# STEP-UP.net
KiCad netlist of a schematic drawn in Altium Designer
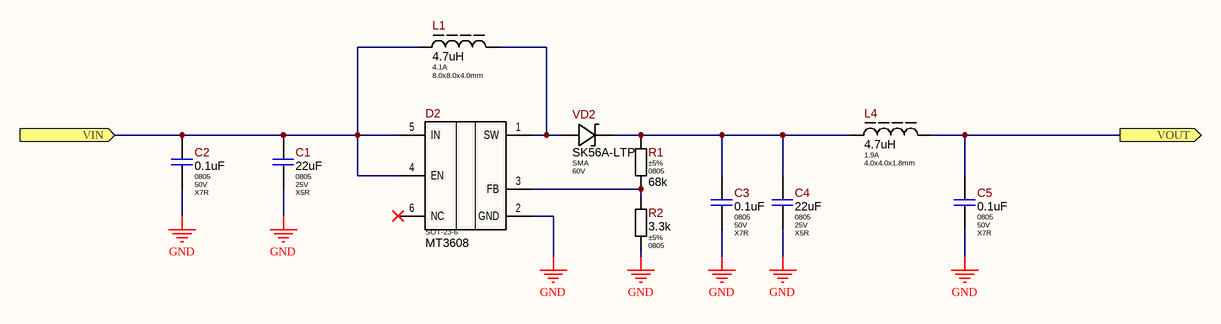
[diagram p0: STEP-UP.SchDoc]

(export (version "E")
  (design (tool "Eeschema 10.0.6"))
  (components
    (comp (ref "C1")
      (value "22uF")
      (footprint "CAP-0805(2012)X125T20")
      (description "22uF 25V X5R ±20% 0805 Ceramic Capacitor RoHS")
      (fields
        (field (name "PACKAGE") "0805")
        (field (name "VOLTAGE") "25V")
        (field (name "DIELECTRIC TYPE") "X5R")
        (field (name "PART NUMBER") "CL21A226MAYNNNE")
        (field (name "MANUFACTURER") "Samsung Electro-Mechanics")
      )
      (libsource (lib "capacitors") (part "CL21A226MAYNNNE"))
    )
    (comp (ref "C2")
      (value "0.1uF")
      (footprint "CAP-0805(2012)X85T10")
      (description "100nF 50V X7R ±10% 0805 Ceramic Capacitor RoHS")
      (fields
        (field (name "PACKAGE") "0805")
        (field (name "VOLTAGE") "50V")
        (field (name "DIELECTRIC TYPE") "X7R")
        (field (name "PART NUMBER") "CL21B104KBCNNNC")
        (field (name "MANUFACTURER") "Samsung Electro-Mechanics")
      )
      (libsource (lib "capacitors") (part "CL21B104KBCNNNC"))
    )
    (comp (ref "C3")
      (value "0.1uF")
      (footprint "CAP-0805(2012)X85T10")
      (description "100nF 50V X7R ±10% 0805 Ceramic Capacitor RoHS")
      (fields
        (field (name "PACKAGE") "0805")
        (field (name "VOLTAGE") "50V")
        (field (name "DIELECTRIC TYPE") "X7R")
        (field (name "PART NUMBER") "CL21B104KBCNNNC")
        (field (name "MANUFACTURER") "Samsung Electro-Mechanics")
      )
      (libsource (lib "capacitors") (part "CL21B104KBCNNNC"))
    )
    (comp (ref "C4")
      (value "22uF")
      (footprint "CAP-0805(2012)X125T20")
      (description "22uF 25V X5R ±20% 0805 Ceramic Capacitor RoHS")
      (fields
        (field (name "PACKAGE") "0805")
        (field (name "VOLTAGE") "25V")
        (field (name "DIELECTRIC TYPE") "X5R")
        (field (name "PART NUMBER") "CL21A226MAYNNNE")
        (field (name "MANUFACTURER") "Samsung Electro-Mechanics")
      )
      (libsource (lib "capacitors") (part "CL21A226MAYNNNE"))
    )
    (comp (ref "C5")
      (value "0.1uF")
      (footprint "CAP-0805(2012)X85T10")
      (description "100nF 50V X7R ±10% 0805 Ceramic Capacitor RoHS")
      (fields
        (field (name "PACKAGE") "0805")
        (field (name "VOLTAGE") "50V")
        (field (name "DIELECTRIC TYPE") "X7R")
        (field (name "PART NUMBER") "CL21B104KBCNNNC")
        (field (name "MANUFACTURER") "Samsung Electro-Mechanics")
      )
      (libsource (lib "capacitors") (part "CL21B104KBCNNNC"))
    )
    (comp (ref "D2")
      (value "MT3608")
      (footprint "MT3608_MED")
      (description "2V-24V Input High Efficiency 1.2MHz 2A Step Up Converter")
      (fields
        (field (name "PACKAGE") "SOT-23-6")
        (field (name "PART NUMBER") "MT3608")
        (field (name "MANUFACTURER") "Aerosemi")
      )
      (libsource (lib "ic") (part "MT3608"))
    )
    (comp (ref "L1")
      (value "4.7uH")
      (footprint "SWPA8040S-Series")
      (description "4.7uH Magnetic-Resin Shielded Wirewound Inductor 4.1 A 25mOhm Max")
      (fields
        (field (name "CURRENT") "4.1A")
        (field (name "PACKAGE") "8.0x8.0x4.0mm")
        (field (name "PART NUMBER") "SWPA8040S4R7NT")
        (field (name "TOLERANCE") "±30%")
      )
      (libsource (lib "inductors") (part "SWPA8040S4R7NT"))
    )
    (comp (ref "L4")
      (value "4.7uH")
      (footprint "SRN4018-Series_1.8mm")
      (description "4.7uH Semi-Shielded Wirewound Inductor 1.9A 84mOhm Max")
      (fields
        (field (name "CURRENT") "1.9A")
        (field (name "PACKAGE") "4.0x4.0x1.8mm")
        (field (name "PART NUMBER") "SRN4018-4R7M")
        (field (name "TOLERANCE") "±20%")
      )
      (libsource (lib "inductors") (part "SRN4018-4R7M"))
    )
    (comp (ref "R1")
      (value "68k")
      (footprint "R_ANY_CHIP_0805_MED")
      (description "2.2 kOhms ±5% 1/8W 0805 Thick Film Resistor")
      (fields
        (field (name "TOLERANCE") "±5%")
        (field (name "PACKAGE") "0805")
        (field (name "PART NUMBER") "RC0805JR-072K2L")
        (field (name "MANUFACTURER") "Yageo")
      )
      (libsource (lib "resistors") (part "RC0805JR-072K2L"))
    )
    (comp (ref "R2")
      (value "3.3k")
      (footprint "R_ANY_CHIP_0805_MED")
      (description "3.3 kOhms ±5%, 1/8W 0805 Thick Film Resistor")
      (fields
        (field (name "TOLERANCE") "±5%")
        (field (name "PACKAGE") "0805")
        (field (name "PART NUMBER") "RC0805JR-073K3L")
        (field (name "MANUFACTURER") "Yageo")
      )
      (libsource (lib "resistors") (part "RC0805JR-073K3L"))
    )
    (comp (ref "VD2")
      (value "SK56A-LTP")
      (footprint "SMA_MED")
      (description "Diode Schottky 60V 5A, SMA")
      (fields
        (field (name "PART NUMBER") "SK56A-LTP")
        (field (name "PACKAGE") "SMA")
        (field (name "VOLTAGE") "60V")
        (field (name "MANUFACTURER") "Micro Commercial Components")
      )
      (libsource (lib "diodes") (part "SK56A-LTP"))
    )
  )
  (nets
    (net (code "1") (name "/VIN") (class "Default")
      (node (ref "C1") (pin "1") (pinfunction "1_1") (pintype "passive"))
      (node (ref "C2") (pin "1") (pinfunction "1_1") (pintype "passive"))
      (node (ref "D2") (pin "4") (pinfunction "EN_4") (pintype "passive"))
      (node (ref "D2") (pin "5") (pinfunction "IN_5") (pintype "passive"))
      (node (ref "L1") (pin "1") (pintype "passive"))
    )
    (net (code "2") (name "/VOUT") (class "Default")
      (node (ref "C5") (pin "1") (pinfunction "1_1") (pintype "passive"))
      (node (ref "L4") (pin "2") (pintype "passive"))
    )
    (net (code "3") (name "GND") (class "Default")
      (node (ref "C1") (pin "2") (pinfunction "2_2") (pintype "passive"))
      (node (ref "C2") (pin "2") (pinfunction "2_2") (pintype "passive"))
      (node (ref "C3") (pin "2") (pinfunction "2_2") (pintype "passive"))
      (node (ref "C4") (pin "2") (pinfunction "2_2") (pintype "passive"))
      (node (ref "C5") (pin "2") (pinfunction "2_2") (pintype "passive"))
      (node (ref "D2") (pin "2") (pinfunction "GND_2") (pintype "passive"))
      (node (ref "R2") (pin "2") (pintype "passive"))
    )
    (net (code "4") (name "Net-(C3-Pad1)") (class "Default")
      (node (ref "C3") (pin "1") (pinfunction "1_1") (pintype "passive"))
      (node (ref "C4") (pin "1") (pinfunction "1_1") (pintype "passive"))
      (node (ref "L4") (pin "1") (pintype "passive"))
      (node (ref "R1") (pin "1") (pintype "passive"))
      (node (ref "VD2") (pin "CA") (pintype "passive"))
    )
    (net (code "5") (name "Net-(D2-FB)") (class "Default")
      (node (ref "D2") (pin "3") (pinfunction "FB_3") (pintype "passive"))
      (node (ref "R1") (pin "2") (pintype "passive"))
      (node (ref "R2") (pin "1") (pintype "passive"))
    )
    (net (code "6") (name "Net-(D2-SW)") (class "Default")
      (node (ref "D2") (pin "1") (pinfunction "SW_1") (pintype "passive"))
      (node (ref "L1") (pin "2") (pintype "passive"))
      (node (ref "VD2") (pin "AN") (pintype "passive"))
    )
    (net (code "7") (name "unconnected-(D2-NC-Pad6)") (class "Default")
      (node (ref "D2") (pin "6") (pinfunction "NC_6") (pintype "passive+no_connect"))
    )
  )
)
